# Single_Supply_ADC_V1_1.net
KiCad netlist of a schematic drawn in Altium Designer
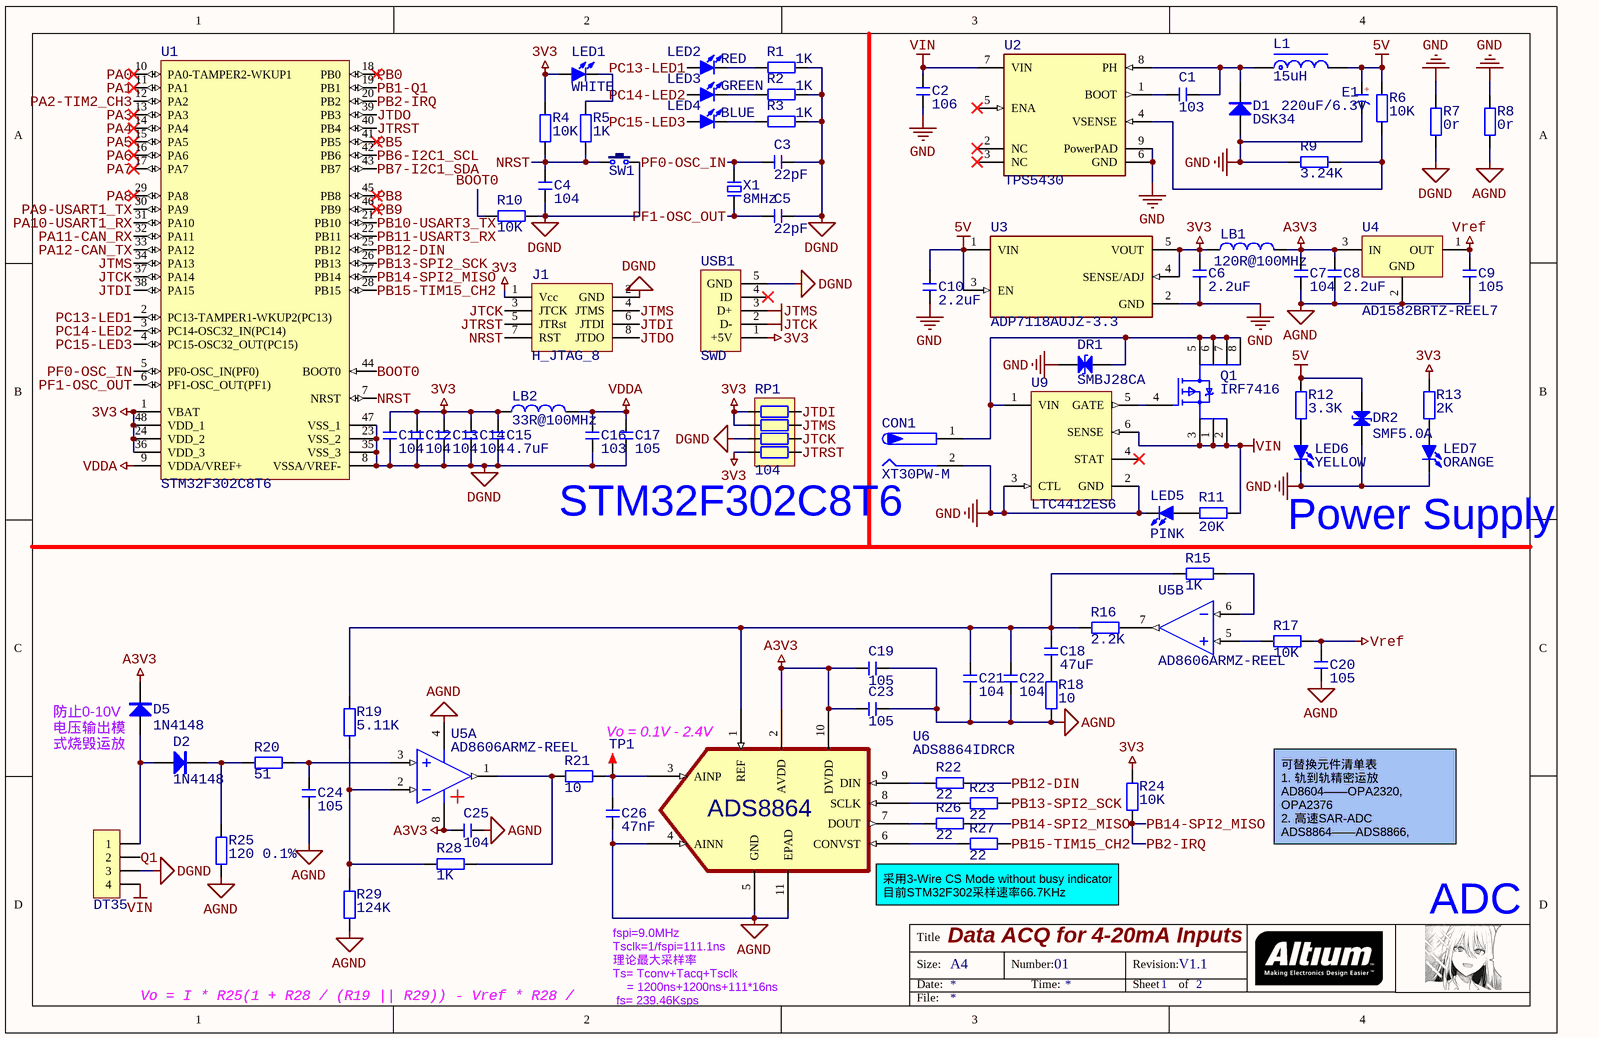
[diagram p0: Single_Supply_ADC_V1.1.SchDoc]

(export (version "E")
  (design (tool "Eeschema 10.0.6"))
  (components
    (comp (ref "C1")
      (value "103")
      (footprint "C 0603_L")
      (description "无极性贴片电容")
      (libsource (lib "3.1   - 电阻-电容-电感") (part "C"))
    )
    (comp (ref "C2")
      (value "106")
      (footprint "C 0805_L")
      (description "无极性贴片电容")
      (libsource (lib "3.1   - 电阻-电容-电感") (part "C"))
    )
    (comp (ref "C3")
      (value "22pF")
      (footprint "C 0603_L")
      (description "无极性贴片电容")
      (libsource (lib "3.1   - 电阻-电容-电感") (part "C"))
    )
    (comp (ref "C4")
      (value "104")
      (footprint "C 0603_L")
      (description "无极性贴片电容")
      (libsource (lib "3.1   - 电阻-电容-电感") (part "C"))
    )
    (comp (ref "C5")
      (value "22pF")
      (footprint "C 0603_L")
      (description "无极性贴片电容")
      (libsource (lib "3.1   - 电阻-电容-电感") (part "C"))
    )
    (comp (ref "C6")
      (value "2.2uF")
      (footprint "C 0603_L")
      (description "无极性贴片电容")
      (libsource (lib "3.1   - 电阻-电容-电感") (part "C"))
    )
    (comp (ref "C7")
      (value "104")
      (footprint "C 0603_L")
      (description "无极性贴片电容")
      (libsource (lib "3.1   - 电阻-电容-电感") (part "C"))
    )
    (comp (ref "C8")
      (value "2.2uF")
      (footprint "C 0603_L")
      (description "无极性贴片电容")
      (libsource (lib "3.1   - 电阻-电容-电感") (part "C"))
    )
    (comp (ref "C9")
      (value "105")
      (footprint "C 0603_L")
      (description "无极性贴片电容")
      (libsource (lib "3.1   - 电阻-电容-电感") (part "C"))
    )
    (comp (ref "C10")
      (value "2.2uF")
      (footprint "C 0603_L")
      (description "无极性贴片电容")
      (libsource (lib "3.1   - 电阻-电容-电感") (part "C"))
    )
    (comp (ref "C11")
      (value "104")
      (footprint "C 0603_L")
      (description "无极性贴片电容")
      (libsource (lib "3.1   - 电阻-电容-电感") (part "C"))
    )
    (comp (ref "C12")
      (value "104")
      (footprint "C 0603_L")
      (description "无极性贴片电容")
      (libsource (lib "3.1   - 电阻-电容-电感") (part "C"))
    )
    (comp (ref "C13")
      (value "104")
      (footprint "C 0603_L")
      (description "无极性贴片电容")
      (libsource (lib "3.1   - 电阻-电容-电感") (part "C"))
    )
    (comp (ref "C14")
      (value "104")
      (footprint "C 0603_L")
      (description "无极性贴片电容")
      (libsource (lib "3.1   - 电阻-电容-电感") (part "C"))
    )
    (comp (ref "C15")
      (value "4.7uF")
      (footprint "C 0603_L")
      (description "无极性贴片电容")
      (libsource (lib "3.1   - 电阻-电容-电感") (part "C"))
    )
    (comp (ref "C16")
      (value "103")
      (footprint "C 0603_L")
      (description "无极性贴片电容")
      (libsource (lib "3.1   - 电阻-电容-电感") (part "C"))
    )
    (comp (ref "C17")
      (value "105")
      (footprint "C 0603_L")
      (description "无极性贴片电容")
      (libsource (lib "3.1   - 电阻-电容-电感") (part "C"))
    )
    (comp (ref "C18")
      (value "47uF")
      (footprint "C 0603_L")
      (description "无极性贴片电容")
      (libsource (lib "3.1   - 电阻-电容-电感") (part "C"))
    )
    (comp (ref "C19")
      (value "105")
      (footprint "C 0603_L")
      (description "无极性贴片电容")
      (libsource (lib "3.1   - 电阻-电容-电感") (part "C"))
    )
    (comp (ref "C20")
      (value "105")
      (footprint "C 0603_L")
      (description "无极性贴片电容")
      (libsource (lib "3.1   - 电阻-电容-电感") (part "C"))
    )
    (comp (ref "C21")
      (value "104")
      (footprint "C 0603_L")
      (description "无极性贴片电容")
      (libsource (lib "3.1   - 电阻-电容-电感") (part "C"))
    )
    (comp (ref "C22")
      (value "104")
      (footprint "C 0603_L")
      (description "无极性贴片电容")
      (libsource (lib "3.1   - 电阻-电容-电感") (part "C"))
    )
    (comp (ref "C23")
      (value "105")
      (footprint "C 0603_L")
      (description "无极性贴片电容")
      (libsource (lib "3.1   - 电阻-电容-电感") (part "C"))
    )
    (comp (ref "C24")
      (value "105")
      (footprint "C 0603_L")
      (description "无极性贴片电容")
      (libsource (lib "3.1   - 电阻-电容-电感") (part "C"))
    )
    (comp (ref "C25")
      (value "104")
      (footprint "C 0603_L")
      (description "无极性贴片电容")
      (libsource (lib "3.1   - 电阻-电容-电感") (part "C"))
    )
    (comp (ref "C26")
      (value "47nF")
      (footprint "C 0603_L")
      (description "无极性贴片电容")
      (libsource (lib "3.1   - 电阻-电容-电感") (part "C"))
    )
    (comp (ref "CON1")
      (value "XT30PW-M")
      (footprint "XT30PW-M")
      (description "XT30PW-M PCB板专用卧式连接器，低温升阻燃插头")
      (libsource (lib "AMASS") (part "XT30PW-M"))
    )
    (comp (ref "D1")
      (value "DSK34")
      (footprint "SOD-123")
      (description "肖特基二极管")
      (libsource (lib "8.1   - 二极管-整流桥") (part "1N5819"))
    )
    (comp (ref "D2")
      (value "1N4148")
      (footprint "SOD-123")
      (description "高速开关二极管")
      (libsource (lib "8.1   - 二极管-整流桥") (part "1N4148"))
    )
    (comp (ref "D5")
      (value "1N4148")
      (footprint "SOD-123")
      (description "高速开关二极管")
      (libsource (lib "8.1   - 二极管-整流桥") (part "1N4148"))
    )
    (comp (ref "DR1")
      (value "SMBJ28CA")
      (footprint "Diode:SMB")
      (description "瞬态电压抑制二极管")
      (libsource (lib "8.1   - 二极管-整流桥") (part "DR"))
    )
    (comp (ref "DR2")
      (value "SMF5.0A")
      (footprint "SOD-323")
      (description "瞬态电压抑制二极管")
      (libsource (lib "8.1   - 二极管-整流桥") (part "DR"))
    )
    (comp (ref "DT35")
      (value "HDR-1X4")
      (footprint "XH2.54-LS-4P")
      (description "4P接插件")
      (libsource (lib "4.6   - 接插件-脚距2.54") (part "Header 4"))
    )
    (comp (ref "E1")
      (value "220uF/6.3V")
      (footprint "CD B(3528)")
      (description "贴片钽电容")
      (libsource (lib "3.1   - 电阻-电容-电感") (part "C-CD"))
    )
    (comp (ref "J1")
      (value "H_JTAG_8")
      (footprint "IDC2.54-LI-2x4P")
      (description "8脚JTAG下载接口")
      (libsource (lib "接插件") (part "H_JTAG_8"))
    )
    (comp (ref "L1")
      (value "15uH")
      (footprint "NR4020")
      (description "NR磁胶电感")
      (libsource (lib "3.1   - 电阻-电容-电感") (part "L-NR"))
    )
    (comp (ref "LB1")
      (value "120R@100MHz")
      (footprint "FB 0603_L")
      (description "磁珠")
      (libsource (lib "3.1   - 电阻-电容-电感") (part "LB"))
    )
    (comp (ref "LB2")
      (value "33R@100MHz")
      (footprint "FB 0603_L")
      (description "磁珠")
      (libsource (lib "3.1   - 电阻-电容-电感") (part "LB"))
    )
    (comp (ref "LED1")
      (value "WHITE")
      (footprint "LED 0603W")
      (description "贴片LED")
      (libsource (lib "9.1   - LED") (part "LED-SMD"))
    )
    (comp (ref "LED2")
      (value "RED")
      (footprint "LED 0603R")
      (description "贴片LED")
      (libsource (lib "9.1   - LED") (part "LED-SMD"))
    )
    (comp (ref "LED3")
      (value "GREEN")
      (footprint "LED 0603G")
      (description "贴片LED")
      (libsource (lib "9.1   - LED") (part "LED-SMD"))
    )
    (comp (ref "LED4")
      (value "BLUE")
      (footprint "LED 0603B")
      (description "贴片LED")
      (libsource (lib "9.1   - LED") (part "LED-SMD"))
    )
    (comp (ref "LED5")
      (value "PINK")
      (footprint "LED 0603R")
      (description "贴片LED")
      (libsource (lib "9.1   - LED") (part "LED-SMD"))
    )
    (comp (ref "LED6")
      (value "YELLOW")
      (footprint "LED 0603R")
      (description "贴片LED")
      (libsource (lib "9.1   - LED") (part "LED-SMD"))
    )
    (comp (ref "LED7")
      (value "ORANGE")
      (footprint "LED 0603R")
      (description "贴片LED")
      (libsource (lib "9.1   - LED") (part "LED-SMD"))
    )
    (comp (ref "Q1")
      (value "IRF7416")
      (footprint "SOP8_L")
      (description "Mosfet Transistor, P Channel, -10 A, -30 V, 20 Mohm, 10 V, -1 V")
      (libsource (lib "MOS") (part "IRF7416TRPBF"))
    )
    (comp (ref "R1")
      (value "1K")
      (footprint "R 0603_L")
      (description "贴片电阻")
      (libsource (lib "3.1   - 电阻-电容-电感") (part "R"))
    )
    (comp (ref "R2")
      (value "1K")
      (footprint "R 0603_L")
      (description "贴片电阻")
      (libsource (lib "3.1   - 电阻-电容-电感") (part "R"))
    )
    (comp (ref "R3")
      (value "1K")
      (footprint "R 0603_L")
      (description "贴片电阻")
      (libsource (lib "3.1   - 电阻-电容-电感") (part "R"))
    )
    (comp (ref "R4")
      (value "10K")
      (footprint "R 0603_L")
      (description "贴片电阻")
      (libsource (lib "3.1   - 电阻-电容-电感") (part "R"))
    )
    (comp (ref "R5")
      (value "1K")
      (footprint "R 0603_L")
      (description "贴片电阻")
      (libsource (lib "3.1   - 电阻-电容-电感") (part "R"))
    )
    (comp (ref "R6")
      (value "10K")
      (footprint "R 0603_L")
      (description "贴片电阻")
      (libsource (lib "3.1   - 电阻-电容-电感") (part "R"))
    )
    (comp (ref "R7")
      (value "0r")
      (footprint "R 0603_L")
      (description "贴片电阻")
      (libsource (lib "3.1   - 电阻-电容-电感") (part "R"))
    )
    (comp (ref "R8")
      (value "0r")
      (footprint "R 0603_L")
      (description "贴片电阻")
      (libsource (lib "3.1   - 电阻-电容-电感") (part "R"))
    )
    (comp (ref "R9")
      (value "3.24K")
      (footprint "R 0603_L")
      (description "贴片电阻")
      (libsource (lib "3.1   - 电阻-电容-电感") (part "R"))
    )
    (comp (ref "R10")
      (value "10K")
      (footprint "R 0603_L")
      (description "贴片电阻")
      (libsource (lib "3.1   - 电阻-电容-电感") (part "R"))
    )
    (comp (ref "R11")
      (value "20K")
      (footprint "R 0603_L")
      (description "贴片电阻")
      (libsource (lib "3.1   - 电阻-电容-电感") (part "R"))
    )
    (comp (ref "R12")
      (value "3.3K")
      (footprint "R 0603_L")
      (description "贴片电阻")
      (libsource (lib "3.1   - 电阻-电容-电感") (part "R"))
    )
    (comp (ref "R13")
      (value "2K")
      (footprint "R 0603_L")
      (description "贴片电阻")
      (libsource (lib "3.1   - 电阻-电容-电感") (part "R"))
    )
    (comp (ref "R15")
      (value "1K")
      (footprint "R 0603_L")
      (description "贴片电阻")
      (libsource (lib "3.1   - 电阻-电容-电感") (part "R"))
    )
    (comp (ref "R16")
      (value "2.2K")
      (footprint "R 0603_L")
      (description "贴片电阻")
      (libsource (lib "3.1   - 电阻-电容-电感") (part "R"))
    )
    (comp (ref "R17")
      (value "10K")
      (footprint "R 0603_L")
      (description "贴片电阻")
      (libsource (lib "3.1   - 电阻-电容-电感") (part "R"))
    )
    (comp (ref "R18")
      (value "10")
      (footprint "R 0603_L")
      (description "贴片电阻")
      (libsource (lib "3.1   - 电阻-电容-电感") (part "R"))
    )
    (comp (ref "R19")
      (value "5.11K")
      (footprint "R 0603_L")
      (description "贴片电阻")
      (libsource (lib "3.1   - 电阻-电容-电感") (part "R"))
    )
    (comp (ref "R20")
      (value "51")
      (footprint "R 0603_L")
      (description "贴片电阻")
      (libsource (lib "3.1   - 电阻-电容-电感") (part "R"))
    )
    (comp (ref "R21")
      (value "10")
      (footprint "R 0603_L")
      (description "贴片电阻")
      (libsource (lib "3.1   - 电阻-电容-电感") (part "R"))
    )
    (comp (ref "R22")
      (value "22")
      (footprint "R 0603_L")
      (description "贴片电阻")
      (libsource (lib "3.1   - 电阻-电容-电感") (part "R"))
    )
    (comp (ref "R23")
      (value "22")
      (footprint "R 0603_L")
      (description "贴片电阻")
      (libsource (lib "3.1   - 电阻-电容-电感") (part "R"))
    )
    (comp (ref "R24")
      (value "10K")
      (footprint "R 0603_L")
      (description "贴片电阻")
      (libsource (lib "3.1   - 电阻-电容-电感") (part "R"))
    )
    (comp (ref "R25")
      (value "120 0.1%")
      (footprint "R 0603_L")
      (description "贴片电阻")
      (libsource (lib "3.1   - 电阻-电容-电感") (part "R"))
    )
    (comp (ref "R26")
      (value "22")
      (footprint "R 0603_L")
      (description "贴片电阻")
      (libsource (lib "3.1   - 电阻-电容-电感") (part "R"))
    )
    (comp (ref "R27")
      (value "22")
      (footprint "R 0603_L")
      (description "贴片电阻")
      (libsource (lib "3.1   - 电阻-电容-电感") (part "R"))
    )
    (comp (ref "R28")
      (value "1K")
      (footprint "R 0603_L")
      (description "贴片电阻")
      (libsource (lib "3.1   - 电阻-电容-电感") (part "R"))
    )
    (comp (ref "R29")
      (value "124K")
      (footprint "R 0603_L")
      (description "贴片电阻")
      (libsource (lib "3.1   - 电阻-电容-电感") (part "R"))
    )
    (comp (ref "RP1")
      (value "104")
      (footprint "RCA-8P4R-0603")
      (description "贴片网络排阻")
      (libsource (lib "3.1   - 电阻-电容-电感") (part "R-8P4R"))
    )
    (comp (ref "SW1")
      (value "6x6x5")
      (footprint "TS 2PIN 6x6x4.8")
      (description "2脚贴片6x6无声硅胶轻触开关")
      (libsource (lib "KEY") (part "TSW SMD-2Pin-6x6"))
    )
    (comp (ref "TP1")
      (value "~")
      (footprint "TEST 1")
      (description "测试点")
      (libsource (lib "15.1 - 未分类器件") (part "TEST"))
    )
    (comp (ref "U1")
      (value "STM32F302C8T6")
      (footprint "LQFP48 7X7_L")
      (libsource (lib "高级IC") (part "STM32F302C8T6"))
    )
    (comp (ref "U2")
      (value "TPS5430")
      (footprint "Texas_Instruments_DDA0008J_IPC_C")
      (description "5.5V to 36V Input, 3A, 500kHz Step-Down Converter 8-SO PowerPAD 0 to 0")
      (libsource (lib "高级IC") (part "TPS5430DDA"))
    )
    (comp (ref "U3")
      (value "ADP7118AUJZ-3.3")
      (footprint "Analog_Devices_Inc_UJ-5_IPC_C")
      (description "20 V, 200 mA, Low Noise,\r\nCMOS LDO Linear Regulator")
      (libsource (lib "高级IC") (part "ADP7118AUJZ-3.3-R7"))
    )
    (comp (ref "U4")
      (value "AD1582BRTZ-REEL7")
      (footprint "SOT23-3L")
      (fields (field (name "MANUFACTURER") "Analog Devices"))
      (libsource (lib "高级IC") (part "AD1582BRTZ-REEL7"))
    )
    (comp (ref "U5")
      (value "AD8606ARMZ-REEL")
      (footprint "RM_8_ADI-L")
      (fields (field (name "GENERIC PART NUMBER") "AD8606") (field (name "MANUFACTURER") "Analog Devices"))
      (libsource (lib "高级IC") (part "AD8606ARMZ-REEL"))
    )
    (comp (ref "U6")
      (value "ADS8864IDRCR")
      (footprint "DRC10_TEX")
      (fields (field (name "COPYRIGHT") "Copyright (C) 2022 Ultra Librarian. All rights reserved."))
      (libsource (lib "高级IC") (part "ADS8864IDRCR"))
    )
    (comp (ref "U9")
      (value "LTC4412ES6")
      (footprint "Texas_Instruments_DDC0006A_0")
      (fields
        (field (name "PARTNUMBER") "LTC4412ES6#TRPBF")
        (field (name "MANUFACTURER") "Linear Technology")
      )
      (libsource (lib "高级IC") (part "LTC4412ES6#TRPBF"))
    )
    (comp (ref "USB1")
      (value "SWD")
      (footprint "USB-MICRO_C")
      (description "微型USB母座")
      (libsource (lib "4.1   - 接口类") (part "USB-5P"))
    )
    (comp (ref "X1")
      (value "8MHz")
      (footprint "OSC 5032-2P")
      (description "2脚无源脚晶振")
      (libsource (lib "10.1 - 保险丝-晶振") (part "XTAL-2P"))
    )
  )
  (nets
    (net (code "1") (name "/BOOT0") (class "Default")
      (node (ref "R10") (pin "2") (pinfunction "2_2") (pintype "passive"))
      (node (ref "U1") (pin "44") (pinfunction "BOOT0_44") (pintype "input"))
    )
    (net (code "2") (name "/JTDI") (class "Default")
      (node (ref "J1") (pin "6") (pinfunction "JTDI_6") (pintype "passive"))
      (node (ref "RP1") (pin "4") (pinfunction "4_4") (pintype "passive"))
      (node (ref "U1") (pin "38") (pinfunction "PA15_38") (pintype "bidirectional"))
    )
    (net (code "3") (name "/JTDO") (class "Default")
      (node (ref "J1") (pin "8") (pinfunction "JTDO_8") (pintype "passive"))
      (node (ref "U1") (pin "39") (pinfunction "PB3_39") (pintype "bidirectional"))
    )
    (net (code "4") (name "/JTRST") (class "Default")
      (node (ref "J1") (pin "5") (pinfunction "JTRst_5") (pintype "passive"))
      (node (ref "RP1") (pin "1") (pinfunction "1_1") (pintype "passive"))
      (node (ref "U1") (pin "40") (pinfunction "PB4_40") (pintype "bidirectional"))
    )
    (net (code "5") (name "/NRST") (class "Default")
      (node (ref "C4") (pin "2") (pinfunction "2_2") (pintype "passive"))
      (node (ref "J1") (pin "7") (pinfunction "RST_7") (pintype "passive"))
      (node (ref "R4") (pin "1") (pinfunction "1_1") (pintype "passive"))
      (node (ref "R5") (pin "1") (pinfunction "1_1") (pintype "passive"))
      (node (ref "SW1") (pin "1") (pinfunction "1_1") (pintype "passive"))
      (node (ref "U1") (pin "7") (pinfunction "NRST_7") (pintype "bidirectional"))
    )
    (net (code "6") (name "/PA0") (class "Default")
      (node (ref "U1") (pin "10") (pinfunction "PA0-TAMPER2-WKUP1_10") (pintype "bidirectional+no_connect"))
    )
    (net (code "7") (name "/PA1") (class "Default")
      (node (ref "U1") (pin "11") (pinfunction "PA1_11") (pintype "bidirectional+no_connect"))
    )
    (net (code "8") (name "/PA2-TIM2_CH3") (class "Default")
      (node (ref "U1") (pin "12") (pinfunction "PA2_12") (pintype "bidirectional"))
    )
    (net (code "9") (name "/PA3") (class "Default")
      (node (ref "U1") (pin "13") (pinfunction "PA3_13") (pintype "bidirectional+no_connect"))
    )
    (net (code "10") (name "/PA4") (class "Default")
      (node (ref "U1") (pin "14") (pinfunction "PA4_14") (pintype "bidirectional+no_connect"))
    )
    (net (code "11") (name "/PA5") (class "Default")
      (node (ref "U1") (pin "15") (pinfunction "PA5_15") (pintype "bidirectional+no_connect"))
    )
    (net (code "12") (name "/PA6") (class "Default")
      (node (ref "U1") (pin "16") (pinfunction "PA6_16") (pintype "bidirectional+no_connect"))
    )
    (net (code "13") (name "/PA7") (class "Default")
      (node (ref "U1") (pin "17") (pinfunction "PA7_17") (pintype "bidirectional+no_connect"))
    )
    (net (code "14") (name "/PA8") (class "Default")
      (node (ref "U1") (pin "29") (pinfunction "PA8_29") (pintype "bidirectional+no_connect"))
    )
    (net (code "15") (name "/PA9-USART1_TX") (class "Default")
      (node (ref "U1") (pin "30") (pinfunction "PA9_30") (pintype "bidirectional"))
    )
    (net (code "16") (name "/PA10-USART1_RX") (class "Default")
      (node (ref "U1") (pin "31") (pinfunction "PA10_31") (pintype "bidirectional"))
    )
    (net (code "17") (name "/PA11-CAN_RX") (class "Default")
      (node (ref "U1") (pin "32") (pinfunction "PA11_32") (pintype "bidirectional"))
    )
    (net (code "18") (name "/PA12-CAN_TX") (class "Default")
      (node (ref "U1") (pin "33") (pinfunction "PA12_33") (pintype "bidirectional"))
    )
    (net (code "19") (name "/PB0") (class "Default")
      (node (ref "U1") (pin "18") (pinfunction "PB0_18") (pintype "bidirectional+no_connect"))
    )
    (net (code "20") (name "/PB1-Q1") (class "Default")
      (node (ref "U1") (pin "19") (pinfunction "PB1_19") (pintype "bidirectional"))
    )
    (net (code "21") (name "/PB5") (class "Default")
      (node (ref "U1") (pin "41") (pinfunction "PB5_41") (pintype "bidirectional+no_connect"))
    )
    (net (code "22") (name "/PB6-I2C1_SCL") (class "Default")
      (node (ref "U1") (pin "42") (pinfunction "PB6_42") (pintype "bidirectional"))
    )
    (net (code "23") (name "/PB7-I2C1_SDA") (class "Default")
      (node (ref "U1") (pin "43") (pinfunction "PB7_43") (pintype "bidirectional"))
    )
    (net (code "24") (name "/PB8") (class "Default")
      (node (ref "U1") (pin "45") (pinfunction "PB8_45") (pintype "bidirectional+no_connect"))
    )
    (net (code "25") (name "/PB9") (class "Default")
      (node (ref "U1") (pin "46") (pinfunction "PB9_46") (pintype "bidirectional+no_connect"))
    )
    (net (code "26") (name "/PB10-USART3_TX") (class "Default")
      (node (ref "U1") (pin "21") (pinfunction "PB10_21") (pintype "bidirectional"))
    )
    (net (code "27") (name "/PB11-USART3_RX") (class "Default")
      (node (ref "U1") (pin "22") (pinfunction "PB11_22") (pintype "bidirectional"))
    )
    (net (code "28") (name "/PB12-DIN") (class "Default")
      (node (ref "R22") (pin "1") (pinfunction "1_1") (pintype "passive"))
      (node (ref "U1") (pin "25") (pinfunction "PB12_25") (pintype "bidirectional"))
    )
    (net (code "29") (name "/PB13-SPI2_SCK") (class "Default")
      (node (ref "R23") (pin "1") (pinfunction "1_1") (pintype "passive"))
      (node (ref "U1") (pin "26") (pinfunction "PB13_26") (pintype "bidirectional"))
    )
    (net (code "30") (name "/PB14-SPI2_MISO") (class "Default")
      (node (ref "R24") (pin "1") (pinfunction "1_1") (pintype "passive"))
      (node (ref "R26") (pin "1") (pinfunction "1_1") (pintype "passive"))
      (node (ref "U1") (pin "20") (pinfunction "PB2_20") (pintype "bidirectional"))
      (node (ref "U1") (pin "27") (pinfunction "PB14_27") (pintype "bidirectional"))
    )
    (net (code "31") (name "/PB15-TIM15_CH2") (class "Default")
      (node (ref "R27") (pin "1") (pinfunction "1_1") (pintype "passive"))
      (node (ref "U1") (pin "28") (pinfunction "PB15_28") (pintype "bidirectional"))
    )
    (net (code "32") (name "/PC13-LED1") (class "Default")
      (node (ref "LED2") (pin "1") (pinfunction "A_1") (pintype "passive"))
      (node (ref "U1") (pin "2") (pinfunction "PC13-TAMPER1-WKUP2(PC13)_2") (pintype "bidirectional"))
    )
    (net (code "33") (name "/PC14-LED2") (class "Default")
      (node (ref "LED3") (pin "1") (pinfunction "A_1") (pintype "passive"))
      (node (ref "U1") (pin "3") (pinfunction "PC14-OSC32_IN(PC14)_3") (pintype "bidirectional"))
    )
    (net (code "34") (name "/PC15-LED3") (class "Default")
      (node (ref "LED4") (pin "1") (pinfunction "A_1") (pintype "passive"))
      (node (ref "U1") (pin "4") (pinfunction "PC15-OSC32_OUT(PC15)_4") (pintype "bidirectional"))
    )
    (net (code "35") (name "/PF0-OSC_IN") (class "Default")
      (node (ref "C3") (pin "2") (pinfunction "2_2") (pintype "passive"))
      (node (ref "U1") (pin "5") (pinfunction "PF0-OSC_IN(PF0)_5") (pintype "bidirectional"))
      (node (ref "X1") (pin "2") (pinfunction "2_2") (pintype "passive"))
    )
    (net (code "36") (name "/PF1-OSC_OUT") (class "Default")
      (node (ref "C5") (pin "2") (pinfunction "2_2") (pintype "passive"))
      (node (ref "U1") (pin "6") (pinfunction "PF1-OSC_OUT(PF1)_6") (pintype "bidirectional"))
      (node (ref "X1") (pin "1") (pinfunction "1_1") (pintype "passive"))
    )
    (net (code "37") (name "/Q1") (class "Default")
      (node (ref "DT35") (pin "2") (pinfunction "2_2") (pintype "passive"))
    )
    (net (code "38") (name "3V3") (class "Default")
      (node (ref "C11") (pin "2") (pinfunction "2_2") (pintype "passive"))
      (node (ref "C12") (pin "2") (pinfunction "2_2") (pintype "passive"))
      (node (ref "C13") (pin "2") (pinfunction "2_2") (pintype "passive"))
      (node (ref "C14") (pin "2") (pinfunction "2_2") (pintype "passive"))
      (node (ref "C15") (pin "2") (pinfunction "2_2") (pintype "passive"))
      (node (ref "C6") (pin "1") (pinfunction "1_1") (pintype "passive"))
      (node (ref "J1") (pin "1") (pinfunction "Vcc_1") (pintype "passive"))
      (node (ref "LB1") (pin "1") (pinfunction "1_1") (pintype "passive"))
      (node (ref "LB2") (pin "1") (pinfunction "1_1") (pintype "passive"))
      (node (ref "LED1") (pin "1") (pinfunction "A_1") (pintype "passive"))
      (node (ref "R13") (pin "2") (pinfunction "2_2") (pintype "passive"))
      (node (ref "R24") (pin "2") (pinfunction "2_2") (pintype "passive"))
      (node (ref "R4") (pin "2") (pinfunction "2_2") (pintype "passive"))
      (node (ref "RP1") (pin "5") (pinfunction "5_5") (pintype "passive"))
      (node (ref "RP1") (pin "6") (pinfunction "6_6") (pintype "passive"))
      (node (ref "RP1") (pin "8") (pinfunction "8_8") (pintype "passive"))
      (node (ref "U1") (pin "1") (pinfunction "VBAT_1") (pintype "power_in"))
      (node (ref "U1") (pin "24") (pinfunction "VDD_2_24") (pintype "power_in"))
      (node (ref "U1") (pin "36") (pinfunction "VDD_3_36") (pintype "power_in"))
      (node (ref "U1") (pin "48") (pinfunction "VDD_1_48") (pintype "power_in"))
      (node (ref "U3") (pin "4") (pinfunction "SENSE/ADJ_4") (pintype "input"))
      (node (ref "U3") (pin "5") (pinfunction "VOUT_5") (pintype "passive"))
      (node (ref "USB1") (pin "1") (pinfunction "+5V_1") (pintype "passive"))
    )
    (net (code "39") (name "5V") (class "Default")
      (node (ref "C10") (pin "1") (pinfunction "1_1") (pintype "passive"))
      (node (ref "DR2") (pin "2") (pinfunction "K_2") (pintype "passive"))
      (node (ref "E1") (pin "1") (pinfunction "A_1") (pintype "passive"))
      (node (ref "L1") (pin "2") (pinfunction "2_2") (pintype "passive"))
      (node (ref "R12") (pin "2") (pinfunction "2_2") (pintype "passive"))
      (node (ref "R6") (pin "2") (pinfunction "2_2") (pintype "passive"))
      (node (ref "U3") (pin "1") (pinfunction "VIN_1") (pintype "power_in"))
      (node (ref "U3") (pin "3") (pinfunction "EN_3") (pintype "input"))
    )
    (net (code "40") (name "A3V3") (class "Default")
      (node (ref "C19") (pin "2") (pinfunction "2_2") (pintype "passive"))
      (node (ref "C23") (pin "2") (pinfunction "2_2") (pintype "passive"))
      (node (ref "C25") (pin "2") (pinfunction "2_2") (pintype "passive"))
      (node (ref "C7") (pin "1") (pinfunction "1_1") (pintype "passive"))
      (node (ref "C8") (pin "1") (pinfunction "1_1") (pintype "passive"))
      (node (ref "D5") (pin "2") (pinfunction "K_2") (pintype "passive"))
      (node (ref "LB1") (pin "2") (pinfunction "2_2") (pintype "passive"))
      (node (ref "U4") (pin "3") (pinfunction "IN_3") (pintype "power_in"))
      (node (ref "U5") (pin "8") (pinfunction "+V_8") (pintype "power_in"))
      (node (ref "U6") (pin "10") (pinfunction "DVDD_10") (pintype "power_in"))
      (node (ref "U6") (pin "2") (pinfunction "AVDD_2") (pintype "power_in"))
    )
    (net (code "41") (name "AGND") (class "Default")
      (node (ref "C19") (pin "1") (pinfunction "1_1") (pintype "passive"))
      (node (ref "C20") (pin "1") (pinfunction "1_1") (pintype "passive"))
      (node (ref "C21") (pin "1") (pinfunction "1_1") (pintype "passive"))
      (node (ref "C22") (pin "1") (pinfunction "1_1") (pintype "passive"))
      (node (ref "C23") (pin "1") (pinfunction "1_1") (pintype "passive"))
      (node (ref "C24") (pin "1") (pinfunction "1_1") (pintype "passive"))
      (node (ref "C25") (pin "1") (pinfunction "1_1") (pintype "passive"))
      (node (ref "C26") (pin "2") (pinfunction "2_2") (pintype "passive"))
      (node (ref "C7") (pin "2") (pinfunction "2_2") (pintype "passive"))
      (node (ref "C8") (pin "2") (pinfunction "2_2") (pintype "passive"))
      (node (ref "C9") (pin "2") (pinfunction "2_2") (pintype "passive"))
      (node (ref "R18") (pin "1") (pinfunction "1_1") (pintype "passive"))
      (node (ref "R25") (pin "1") (pinfunction "1_1") (pintype "passive"))
      (node (ref "R29") (pin "1") (pinfunction "1_1") (pintype "passive"))
      (node (ref "R8") (pin "2") (pinfunction "2_2") (pintype "passive"))
      (node (ref "U4") (pin "2") (pinfunction "GND_2") (pintype "power_in"))
      (node (ref "U5") (pin "4") (pinfunction "-V_4") (pintype "power_in"))
      (node (ref "U6") (pin "11") (pinfunction "EPAD_11") (pintype "passive"))
      (node (ref "U6") (pin "4") (pinfunction "AINN_4") (pintype "input"))
      (node (ref "U6") (pin "5") (pinfunction "GND_5") (pintype "power_in"))
    )
    (net (code "42") (name "DGND") (class "Default")
      (node (ref "C11") (pin "1") (pinfunction "1_1") (pintype "passive"))
      (node (ref "C12") (pin "1") (pinfunction "1_1") (pintype "passive"))
      (node (ref "C13") (pin "1") (pinfunction "1_1") (pintype "passive"))
      (node (ref "C14") (pin "1") (pinfunction "1_1") (pintype "passive"))
      (node (ref "C15") (pin "1") (pinfunction "1_1") (pintype "passive"))
      (node (ref "C16") (pin "1") (pinfunction "1_1") (pintype "passive"))
      (node (ref "C17") (pin "1") (pinfunction "1_1") (pintype "passive"))
      (node (ref "C3") (pin "1") (pinfunction "1_1") (pintype "passive"))
      (node (ref "C4") (pin "1") (pinfunction "1_1") (pintype "passive"))
      (node (ref "C5") (pin "1") (pinfunction "1_1") (pintype "passive"))
      (node (ref "DT35") (pin "3") (pinfunction "3_3") (pintype "passive"))
      (node (ref "J1") (pin "2") (pinfunction "GND_2") (pintype "passive"))
      (node (ref "R1") (pin "2") (pinfunction "2_2") (pintype "passive"))
      (node (ref "R10") (pin "1") (pinfunction "1_1") (pintype "passive"))
      (node (ref "R2") (pin "2") (pinfunction "2_2") (pintype "passive"))
      (node (ref "R3") (pin "2") (pinfunction "2_2") (pintype "passive"))
      (node (ref "R7") (pin "2") (pinfunction "2_2") (pintype "passive"))
      (node (ref "RP1") (pin "7") (pinfunction "7_7") (pintype "passive"))
      (node (ref "SW1") (pin "2") (pinfunction "2_2") (pintype "passive"))
      (node (ref "U1") (pin "23") (pinfunction "VSS_2_23") (pintype "power_in"))
      (node (ref "U1") (pin "35") (pinfunction "VSS_3_35") (pintype "power_in"))
      (node (ref "U1") (pin "47") (pinfunction "VSS_1_47") (pintype "power_in"))
      (node (ref "U1") (pin "8") (pinfunction "VSSA/VREF-_8") (pintype "power_in"))
      (node (ref "USB1") (pin "5") (pinfunction "GND_5") (pintype "passive"))
    )
    (net (code "43") (name "GND") (class "Default")
      (node (ref "C10") (pin "2") (pinfunction "2_2") (pintype "passive"))
      (node (ref "C2") (pin "1") (pinfunction "1_1") (pintype "passive"))
      (node (ref "C6") (pin "2") (pinfunction "2_2") (pintype "passive"))
      (node (ref "CON1") (pin "2") (pintype "power_in"))
      (node (ref "D1") (pin "1") (pinfunction "A_1") (pintype "passive"))
      (node (ref "DR1") (pin "2") (pinfunction "K_2") (pintype "passive"))
      (node (ref "DR2") (pin "1") (pinfunction "A_1") (pintype "passive"))
      (node (ref "E1") (pin "2") (pinfunction "K_2") (pintype "passive"))
      (node (ref "LED5") (pin "2") (pinfunction "K_2") (pintype "passive"))
      (node (ref "LED6") (pin "2") (pinfunction "K_2") (pintype "passive"))
      (node (ref "LED7") (pin "2") (pinfunction "K_2") (pintype "passive"))
      (node (ref "R7") (pin "1") (pinfunction "1_1") (pintype "passive"))
      (node (ref "R8") (pin "1") (pinfunction "1_1") (pintype "passive"))
      (node (ref "R9") (pin "2") (pinfunction "2_2") (pintype "passive"))
      (node (ref "U2") (pin "6") (pinfunction "GND_6") (pintype "power_in"))
      (node (ref "U2") (pin "9") (pinfunction "PowerPAD_9") (pintype "power_in"))
      (node (ref "U3") (pin "2") (pinfunction "GND_2") (pintype "power_in"))
      (node (ref "U9") (pin "2") (pinfunction "GND_2") (pintype "power_in"))
      (node (ref "U9") (pin "3") (pinfunction "CTL_3") (pintype "input"))
    )
    (net (code "44") (name "JTCK") (class "Default")
      (node (ref "J1") (pin "3") (pinfunction "JTCK_3") (pintype "passive"))
      (node (ref "RP1") (pin "2") (pinfunction "2_2") (pintype "passive"))
      (node (ref "U1") (pin "37") (pinfunction "PA14_37") (pintype "bidirectional"))
      (node (ref "USB1") (pin "2") (pinfunction "D-_2") (pintype "passive"))
    )
    (net (code "45") (name "JTMS") (class "Default")
      (node (ref "J1") (pin "4") (pinfunction "JTMS_4") (pintype "passive"))
      (node (ref "RP1") (pin "3") (pinfunction "3_3") (pintype "passive"))
      (node (ref "U1") (pin "34") (pinfunction "PA13_34") (pintype "bidirectional"))
      (node (ref "USB1") (pin "3") (pinfunction "D+_3") (pintype "passive"))
    )
    (net (code "46") (name "Net-(C18-Pad1)") (class "Default")
      (node (ref "C18") (pin "1") (pinfunction "1_1") (pintype "passive"))
      (node (ref "R18") (pin "2") (pinfunction "2_2") (pintype "passive"))
    )
    (net (code "47") (name "Net-(D1-K)") (class "Default")
      (node (ref "C1") (pin "1") (pinfunction "1_1") (pintype "passive"))
      (node (ref "D1") (pin "2") (pinfunction "K_2") (pintype "passive"))
      (node (ref "L1") (pin "1") (pinfunction "1_1") (pintype "passive"))
      (node (ref "U2") (pin "8") (pinfunction "PH_8") (pintype "input"))
    )
    (net (code "48") (name "Net-(D2-A)") (class "Default")
      (node (ref "D2") (pin "1") (pinfunction "A_1") (pintype "passive"))
      (node (ref "D5") (pin "1") (pinfunction "A_1") (pintype "passive"))
      (node (ref "DT35") (pin "1") (pinfunction "1_1") (pintype "passive"))
    )
    (net (code "49") (name "Net-(D2-K)") (class "Default")
      (node (ref "D2") (pin "2") (pinfunction "K_2") (pintype "passive"))
      (node (ref "R20") (pin "2") (pinfunction "2_2") (pintype "passive"))
      (node (ref "R25") (pin "2") (pinfunction "2_2") (pintype "passive"))
    )
    (net (code "50") (name "Net-(DR1-A)") (class "Default")
      (node (ref "CON1") (pin "1") (pintype "power_in"))
      (node (ref "DR1") (pin "1") (pinfunction "A_1") (pintype "passive"))
      (node (ref "Q1") (pin "5") (pinfunction "D_5") (pintype "passive"))
      (node (ref "Q1") (pin "6") (pinfunction "D_6") (pintype "passive"))
      (node (ref "Q1") (pin "7") (pinfunction "D_7") (pintype "passive"))
      (node (ref "Q1") (pin "8") (pinfunction "D_8") (pintype "passive"))
      (node (ref "U9") (pin "1") (pinfunction "VIN_1") (pintype "power_in"))
    )
    (net (code "51") (name "Net-(LED1-K)") (class "Default")
      (node (ref "LED1") (pin "2") (pinfunction "K_2") (pintype "passive"))
      (node (ref "R5") (pin "2") (pinfunction "2_2") (pintype "passive"))
    )
    (net (code "52") (name "Net-(LED2-K)") (class "Default")
      (node (ref "LED2") (pin "2") (pinfunction "K_2") (pintype "passive"))
      (node (ref "R1") (pin "1") (pinfunction "1_1") (pintype "passive"))
    )
    (net (code "53") (name "Net-(LED3-K)") (class "Default")
      (node (ref "LED3") (pin "2") (pinfunction "K_2") (pintype "passive"))
      (node (ref "R2") (pin "1") (pinfunction "1_1") (pintype "passive"))
    )
    (net (code "54") (name "Net-(LED4-K)") (class "Default")
      (node (ref "LED4") (pin "2") (pinfunction "K_2") (pintype "passive"))
      (node (ref "R3") (pin "1") (pinfunction "1_1") (pintype "passive"))
    )
    (net (code "55") (name "Net-(LED5-A)") (class "Default")
      (node (ref "LED5") (pin "1") (pinfunction "A_1") (pintype "passive"))
      (node (ref "R11") (pin "2") (pinfunction "2_2") (pintype "passive"))
    )
    (net (code "56") (name "Net-(LED6-A)") (class "Default")
      (node (ref "LED6") (pin "1") (pinfunction "A_1") (pintype "passive"))
      (node (ref "R12") (pin "1") (pinfunction "1_1") (pintype "passive"))
    )
    (net (code "57") (name "Net-(LED7-A)") (class "Default")
      (node (ref "LED7") (pin "1") (pinfunction "A_1") (pintype "passive"))
      (node (ref "R13") (pin "1") (pinfunction "1_1") (pintype "passive"))
    )
    (net (code "58") (name "Net-(Q1-G)") (class "Default")
      (node (ref "Q1") (pin "4") (pinfunction "G_4") (pintype "passive"))
      (node (ref "U9") (pin "5") (pinfunction "GATE_5") (pintype "output"))
    )
    (net (code "59") (name "Net-(U2-BOOT)") (class "Default")
      (node (ref "C1") (pin "2") (pinfunction "2_2") (pintype "passive"))
      (node (ref "U2") (pin "1") (pinfunction "BOOT_1") (pintype "output"))
    )
    (net (code "60") (name "Net-(U2-VSENSE)") (class "Default")
      (node (ref "R6") (pin "1") (pinfunction "1_1") (pintype "passive"))
      (node (ref "R9") (pin "1") (pinfunction "1_1") (pintype "passive"))
      (node (ref "U2") (pin "4") (pinfunction "VSENSE_4") (pintype "input"))
    )
    (net (code "61") (name "Net-(U5A-+IN_A)") (class "Default")
      (node (ref "C24") (pin "2") (pinfunction "2_2") (pintype "passive"))
      (node (ref "R20") (pin "1") (pinfunction "1_1") (pintype "passive"))
      (node (ref "U5") (pin "3") (pinfunction "+IN_A_3") (pintype "input"))
    )
    (net (code "62") (name "Net-(U5A--IN_A)") (class "Default")
      (node (ref "R19") (pin "1") (pinfunction "1_1") (pintype "passive"))
      (node (ref "R28") (pin "2") (pinfunction "2_2") (pintype "passive"))
      (node (ref "R29") (pin "2") (pinfunction "2_2") (pintype "passive"))
      (node (ref "U5") (pin "2") (pinfunction "-IN_A_2") (pintype "input"))
    )
    (net (code "63") (name "Net-(U5A-OUT_A)") (class "Default")
      (node (ref "R21") (pin "2") (pinfunction "2_2") (pintype "passive"))
      (node (ref "R28") (pin "1") (pinfunction "1_1") (pintype "passive"))
      (node (ref "U5") (pin "1") (pinfunction "OUT_A_1") (pintype "output"))
    )
    (net (code "64") (name "Net-(U5B-+IN_B)") (class "Default")
      (node (ref "R17") (pin "2") (pinfunction "2_2") (pintype "passive"))
      (node (ref "U5") (pin "5") (pinfunction "+IN_B_5") (pintype "input"))
    )
    (net (code "65") (name "Net-(U5B--IN_B)") (class "Default")
      (node (ref "R15") (pin "1") (pinfunction "1_1") (pintype "passive"))
      (node (ref "U5") (pin "6") (pinfunction "-IN_B_6") (pintype "input"))
    )
    (net (code "66") (name "Net-(U5B-OUT_B)") (class "Default")
      (node (ref "R16") (pin "1") (pinfunction "1_1") (pintype "passive"))
      (node (ref "U5") (pin "7") (pinfunction "OUT_B_7") (pintype "output"))
    )
    (net (code "67") (name "Net-(U6-AINP)") (class "Default")
      (node (ref "C26") (pin "1") (pinfunction "1_1") (pintype "passive"))
      (node (ref "R21") (pin "1") (pinfunction "1_1") (pintype "passive"))
      (node (ref "TP1") (pin "1") (pinfunction "1_1") (pintype "passive"))
      (node (ref "U6") (pin "3") (pinfunction "AINP_3") (pintype "input"))
    )
    (net (code "68") (name "Net-(U6-CONVST)") (class "Default")
      (node (ref "R27") (pin "2") (pinfunction "2_2") (pintype "passive"))
      (node (ref "U6") (pin "6") (pinfunction "CONVST_6") (pintype "input"))
    )
    (net (code "69") (name "Net-(U6-DIN)") (class "Default")
      (node (ref "R22") (pin "2") (pinfunction "2_2") (pintype "passive"))
      (node (ref "U6") (pin "9") (pinfunction "DIN_9") (pintype "input"))
    )
    (net (code "70") (name "Net-(U6-DOUT)") (class "Default")
      (node (ref "R26") (pin "2") (pinfunction "2_2") (pintype "passive"))
      (node (ref "U6") (pin "7") (pinfunction "DOUT_7") (pintype "output"))
    )
    (net (code "71") (name "Net-(U6-REF)") (class "Default")
      (node (ref "C18") (pin "2") (pinfunction "2_2") (pintype "passive"))
      (node (ref "C21") (pin "2") (pinfunction "2_2") (pintype "passive"))
      (node (ref "C22") (pin "2") (pinfunction "2_2") (pintype "passive"))
      (node (ref "R15") (pin "2") (pinfunction "2_2") (pintype "passive"))
      (node (ref "R16") (pin "2") (pinfunction "2_2") (pintype "passive"))
      (node (ref "R19") (pin "2") (pinfunction "2_2") (pintype "passive"))
      (node (ref "U6") (pin "1") (pinfunction "REF_1") (pintype "input"))
    )
    (net (code "72") (name "Net-(U6-SCLK)") (class "Default")
      (node (ref "R23") (pin "2") (pinfunction "2_2") (pintype "passive"))
      (node (ref "U6") (pin "8") (pinfunction "SCLK_8") (pintype "input"))
    )
    (net (code "73") (name "VDDA") (class "Default")
      (node (ref "C16") (pin "2") (pinfunction "2_2") (pintype "passive"))
      (node (ref "C17") (pin "2") (pinfunction "2_2") (pintype "passive"))
      (node (ref "LB2") (pin "2") (pinfunction "2_2") (pintype "passive"))
      (node (ref "U1") (pin "9") (pinfunction "VDDA/VREF+_9") (pintype "power_in"))
    )
    (net (code "74") (name "VIN") (class "Default")
      (node (ref "C2") (pin "2") (pinfunction "2_2") (pintype "passive"))
      (node (ref "DT35") (pin "4") (pinfunction "4_4") (pintype "passive"))
      (node (ref "Q1") (pin "1") (pinfunction "S_1") (pintype "passive"))
      (node (ref "Q1") (pin "2") (pinfunction "S_2") (pintype "passive"))
      (node (ref "Q1") (pin "3") (pinfunction "S_3") (pintype "passive"))
      (node (ref "R11") (pin "1") (pinfunction "1_1") (pintype "passive"))
      (node (ref "U2") (pin "7") (pinfunction "VIN_7") (pintype "power_in"))
      (node (ref "U9") (pin "6") (pinfunction "SENSE_6") (pintype "input"))
    )
    (net (code "75") (name "Vref") (class "Default")
      (node (ref "C20") (pin "2") (pinfunction "2_2") (pintype "passive"))
      (node (ref "C9") (pin "1") (pinfunction "1_1") (pintype "passive"))
      (node (ref "R17") (pin "1") (pinfunction "1_1") (pintype "passive"))
      (node (ref "U4") (pin "1") (pinfunction "OUT_1") (pintype "power_in"))
    )
    (net (code "76") (name "unconnected-(U2-ENA-Pad5)") (class "Default")
      (node (ref "U2") (pin "5") (pinfunction "ENA_5") (pintype "input+no_connect"))
    )
    (net (code "77") (name "unconnected-(U2-NC-Pad2)") (class "Default")
      (node (ref "U2") (pin "2") (pinfunction "NC_2") (pintype "passive+no_connect"))
    )
    (net (code "78") (name "unconnected-(U2-NC-Pad3)") (class "Default")
      (node (ref "U2") (pin "3") (pinfunction "NC_3") (pintype "passive+no_connect"))
    )
    (net (code "79") (name "unconnected-(U9-STAT-Pad4)") (class "Default")
      (node (ref "U9") (pin "4") (pinfunction "STAT_4") (pintype "open_collector+no_connect"))
    )
    (net (code "80") (name "unconnected-(USB1-ID-Pad4)") (class "Default")
      (node (ref "USB1") (pin "4") (pinfunction "ID_4") (pintype "passive+no_connect"))
    )
  )
)
